# water_controller.net
KiCad netlist of a schematic drawn in EAGLE
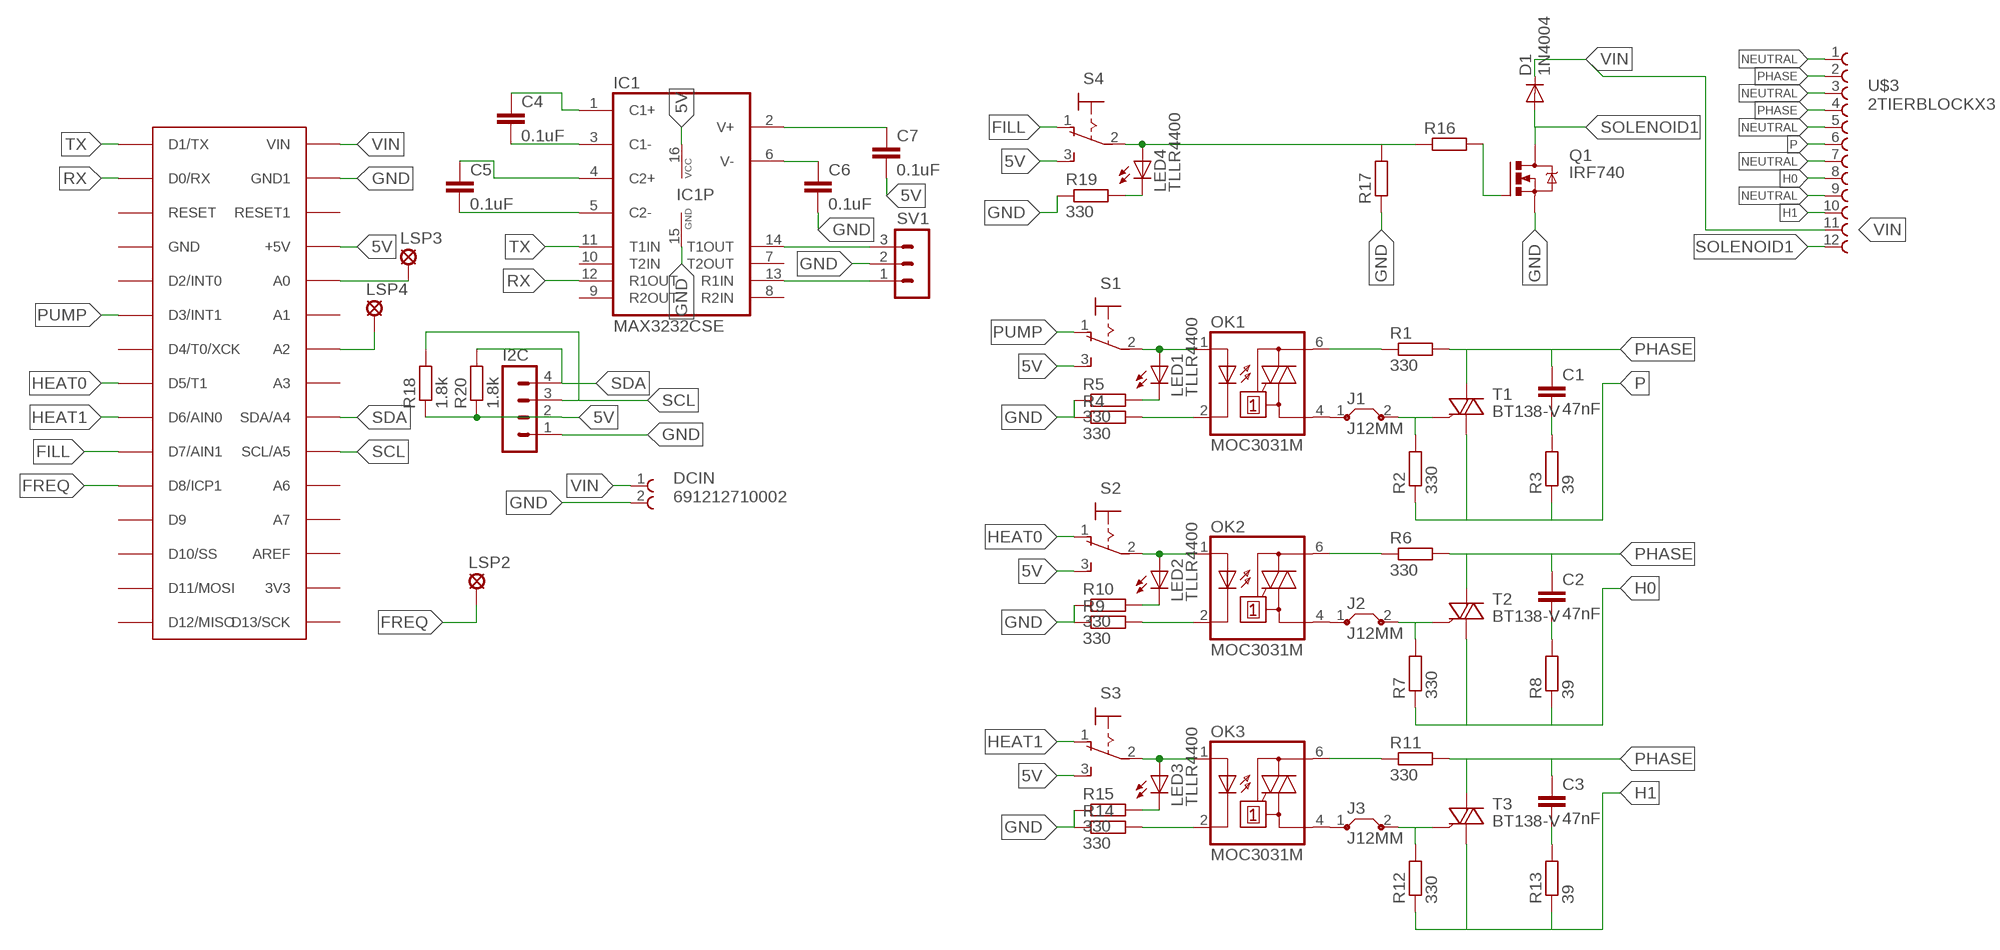
[diagram p0: schematic, sheet 1]

(export (version "E")
  (design (tool "Eeschema 10.0.6"))
  (components
    (comp (ref "C1")
      (value "47nF")
      (footprint "eagle-import:C150-064X183")
      (libsource (lib "eagle-import") (part "C-EU150-064X183"))
    )
    (comp (ref "C2")
      (value "47nF")
      (footprint "eagle-import:C150-064X183")
      (libsource (lib "eagle-import") (part "C-EU150-064X183"))
    )
    (comp (ref "C3")
      (value "47nF")
      (footprint "eagle-import:C150-064X183")
      (libsource (lib "eagle-import") (part "C-EU150-064X183"))
    )
    (comp (ref "C4")
      (value "0.1uF")
      (footprint "eagle-import:C0805")
      (libsource (lib "eagle-import") (part "C-EUC0805"))
    )
    (comp (ref "C5")
      (value "0.1uF")
      (footprint "eagle-import:C0805")
      (libsource (lib "eagle-import") (part "C-EUC0805"))
    )
    (comp (ref "C6")
      (value "0.1uF")
      (footprint "eagle-import:C0805")
      (libsource (lib "eagle-import") (part "C-EUC0805"))
    )
    (comp (ref "C7")
      (value "0.1uF")
      (footprint "eagle-import:C0805")
      (libsource (lib "eagle-import") (part "C-EUC0805"))
    )
    (comp (ref "D1")
      (value "1N4004")
      (footprint "eagle-import:DO41-10")
      (libsource (lib "eagle-import") (part "1N4004"))
    )
    (comp (ref "DCIN")
      (value "691212710002")
      (footprint "eagle-import:691212710002")
      (libsource (lib "eagle-import") (part "691212710002"))
    )
    (comp (ref "I2C")
      (value "MA04-1")
      (footprint "eagle-import:MA04-1")
      (libsource (lib "eagle-import") (part "MA04-1"))
    )
    (comp (ref "IC1")
      (value "MAX3232CSE")
      (footprint "eagle-import:SO16")
      (libsource (lib "eagle-import") (part "MAX3232SEC"))
    )
    (comp (ref "J1")
      (value "J12MM")
      (footprint "eagle-import:12")
      (libsource (lib "eagle-import") (part "J12MM"))
    )
    (comp (ref "J2")
      (value "J12MM")
      (footprint "eagle-import:12")
      (libsource (lib "eagle-import") (part "J12MM"))
    )
    (comp (ref "J3")
      (value "J12MM")
      (footprint "eagle-import:12")
      (libsource (lib "eagle-import") (part "J12MM"))
    )
    (comp (ref "LED1")
      (value "TLLR4400")
      (footprint "eagle-import:LED3MM")
      (fields (field (name "MF") "VISHAY SEMICONDUCTOR"))
      (libsource (lib "eagle-import") (part "TLLR4400"))
    )
    (comp (ref "LED2")
      (value "TLLR4400")
      (footprint "eagle-import:LED3MM")
      (fields (field (name "MF") "VISHAY SEMICONDUCTOR"))
      (libsource (lib "eagle-import") (part "TLLR4400"))
    )
    (comp (ref "LED3")
      (value "TLLR4400")
      (footprint "eagle-import:LED3MM")
      (fields (field (name "MF") "VISHAY SEMICONDUCTOR"))
      (libsource (lib "eagle-import") (part "TLLR4400"))
    )
    (comp (ref "LED4")
      (value "TLLR4400")
      (footprint "eagle-import:LED3MM")
      (fields (field (name "MF") "VISHAY SEMICONDUCTOR"))
      (libsource (lib "eagle-import") (part "TLLR4400"))
    )
    (comp (ref "LSP2")
      (value "LSP11")
      (footprint "eagle-import:LSP11")
      (libsource (lib "eagle-import") (part "LSP11"))
    )
    (comp (ref "LSP3")
      (value "LSP11")
      (footprint "eagle-import:LSP11")
      (libsource (lib "eagle-import") (part "LSP11"))
    )
    (comp (ref "LSP4")
      (value "LSP11")
      (footprint "eagle-import:LSP11")
      (libsource (lib "eagle-import") (part "LSP11"))
    )
    (comp (ref "OK1")
      (value "MOC3031M")
      (footprint "eagle-import:DIL06")
      (fields (field (name "MF") "FAIRCHILD SEMICONDUCTOR") (field (name "MPN") "MOC3063"))
      (libsource (lib "eagle-import") (part "MOC3031M"))
    )
    (comp (ref "OK2")
      (value "MOC3031M")
      (footprint "eagle-import:DIL06")
      (fields (field (name "MF") "FAIRCHILD SEMICONDUCTOR") (field (name "MPN") "MOC3063"))
      (libsource (lib "eagle-import") (part "MOC3031M"))
    )
    (comp (ref "OK3")
      (value "MOC3031M")
      (footprint "eagle-import:DIL06")
      (fields (field (name "MF") "FAIRCHILD SEMICONDUCTOR") (field (name "MPN") "MOC3063"))
      (libsource (lib "eagle-import") (part "MOC3031M"))
    )
    (comp (ref "Q1")
      (value "IRF740")
      (footprint "eagle-import:TO220BV")
      (libsource (lib "eagle-import") (part "IRF740"))
    )
    (comp (ref "R1")
      (value "330")
      (footprint "eagle-import:M1206")
      (libsource (lib "eagle-import") (part "R-EU_M1206"))
    )
    (comp (ref "R2")
      (value "330")
      (footprint "eagle-import:M1206")
      (libsource (lib "eagle-import") (part "R-EU_M1206"))
    )
    (comp (ref "R3")
      (value "39")
      (footprint "eagle-import:M1206")
      (libsource (lib "eagle-import") (part "R-EU_M1206"))
    )
    (comp (ref "R4")
      (value "330")
      (footprint "eagle-import:R1206")
      (libsource (lib "eagle-import") (part "R-EU_R1206"))
    )
    (comp (ref "R5")
      (value "330")
      (footprint "eagle-import:R1206")
      (libsource (lib "eagle-import") (part "R-EU_R1206"))
    )
    (comp (ref "R6")
      (value "330")
      (footprint "eagle-import:M1206")
      (libsource (lib "eagle-import") (part "R-EU_M1206"))
    )
    (comp (ref "R7")
      (value "330")
      (footprint "eagle-import:M1206")
      (libsource (lib "eagle-import") (part "R-EU_M1206"))
    )
    (comp (ref "R8")
      (value "39")
      (footprint "eagle-import:M1206")
      (libsource (lib "eagle-import") (part "R-EU_M1206"))
    )
    (comp (ref "R9")
      (value "330")
      (footprint "eagle-import:R1206")
      (libsource (lib "eagle-import") (part "R-EU_R1206"))
    )
    (comp (ref "R10")
      (value "330")
      (footprint "eagle-import:R1206")
      (libsource (lib "eagle-import") (part "R-EU_R1206"))
    )
    (comp (ref "R11")
      (value "330")
      (footprint "eagle-import:M1206")
      (libsource (lib "eagle-import") (part "R-EU_M1206"))
    )
    (comp (ref "R12")
      (value "330")
      (footprint "eagle-import:M1206")
      (libsource (lib "eagle-import") (part "R-EU_M1206"))
    )
    (comp (ref "R13")
      (value "39")
      (footprint "eagle-import:M1206")
      (libsource (lib "eagle-import") (part "R-EU_M1206"))
    )
    (comp (ref "R14")
      (value "330")
      (footprint "eagle-import:R1206")
      (libsource (lib "eagle-import") (part "R-EU_R1206"))
    )
    (comp (ref "R15")
      (value "330")
      (footprint "eagle-import:R1206")
      (libsource (lib "eagle-import") (part "R-EU_R1206"))
    )
    (comp (ref "R16")
      (value "R-EU_0204/7")
      (footprint "eagle-import:0204_7")
      (libsource (lib "eagle-import") (part "R-EU_0204/7"))
    )
    (comp (ref "R17")
      (value "R-EU_M1206")
      (footprint "eagle-import:M1206")
      (libsource (lib "eagle-import") (part "R-EU_M1206"))
    )
    (comp (ref "R18")
      (value "1.8k")
      (footprint "eagle-import:R1206")
      (libsource (lib "eagle-import") (part "resistor_R-EU_R1206"))
    )
    (comp (ref "R19")
      (value "330")
      (footprint "eagle-import:R1206")
      (libsource (lib "eagle-import") (part "R-EU_R1206"))
    )
    (comp (ref "R20")
      (value "1.8k")
      (footprint "eagle-import:R1206")
      (libsource (lib "eagle-import") (part "resistor_R-EU_R1206"))
    )
    (comp (ref "S1")
      (value "M9040P")
      (footprint "eagle-import:M9040P")
      (libsource (lib "eagle-import") (part "M9040P"))
    )
    (comp (ref "S2")
      (value "M9040P")
      (footprint "eagle-import:M9040P")
      (libsource (lib "eagle-import") (part "M9040P"))
    )
    (comp (ref "S3")
      (value "M9040P")
      (footprint "eagle-import:M9040P")
      (libsource (lib "eagle-import") (part "M9040P"))
    )
    (comp (ref "S4")
      (value "M9040P")
      (footprint "eagle-import:M9040P")
      (libsource (lib "eagle-import") (part "M9040P"))
    )
    (comp (ref "SV1")
      (value "MA03-1")
      (footprint "eagle-import:MA03-1")
      (libsource (lib "eagle-import") (part "MA03-1"))
    )
    (comp (ref "T1")
      (value "BT138-V")
      (footprint "eagle-import:TO220BV")
      (libsource (lib "eagle-import") (part "BT138-V"))
    )
    (comp (ref "T2")
      (value "BT138-V")
      (footprint "eagle-import:TO220BV")
      (libsource (lib "eagle-import") (part "BT138-V"))
    )
    (comp (ref "T3")
      (value "BT138-V")
      (footprint "eagle-import:TO220BV")
      (libsource (lib "eagle-import") (part "BT138-V"))
    )
    (comp (ref "U$1")
      (value "ARDUINONANO")
      (footprint "eagle-import:PDIP-32")
      (libsource (lib "eagle-import") (part "ARDUINONANO"))
    )
    (comp (ref "U$3")
      (value "2TIERBLOCKX3")
      (footprint "eagle-import:2TIERX3")
      (libsource (lib "eagle-import") (part "2TIERBLOCKX3"))
    )
  )
  (nets
    (net (code "1") (name "5V") (class "Default")
      (node (ref "C7") (pin "2") (pinfunction "2_2") (pintype "passive"))
      (node (ref "I2C") (pin "2") (pinfunction "2_2") (pintype "passive"))
      (node (ref "IC1") (pin "16") (pinfunction "VCC_16") (pintype "power_in"))
      (node (ref "R18") (pin "1") (pinfunction "1_1") (pintype "passive"))
      (node (ref "R20") (pin "1") (pinfunction "1_1") (pintype "passive"))
      (node (ref "S1") (pin "3") (pinfunction "S_3") (pintype "passive"))
      (node (ref "S2") (pin "3") (pinfunction "S_3") (pintype "passive"))
      (node (ref "S3") (pin "3") (pinfunction "S_3") (pintype "passive"))
      (node (ref "S4") (pin "3") (pinfunction "S_3") (pintype "passive"))
      (node (ref "U$1") (pin "+5V") (pinfunction "+5V_+5V") (pintype "bidirectional"))
    )
    (net (code "2") (name "FILL") (class "Default")
      (node (ref "S4") (pin "1") (pinfunction "O_1") (pintype "passive"))
      (node (ref "U$1") (pin "D7") (pinfunction "D7/AIN1_D7") (pintype "bidirectional"))
    )
    (net (code "3") (name "FREQ") (class "Default")
      (node (ref "LSP2") (pin "MP") (pinfunction "MP_MP") (pintype "passive"))
      (node (ref "U$1") (pin "D8") (pinfunction "D8/ICP1_D8") (pintype "bidirectional"))
    )
    (net (code "4") (name "GND") (class "Default")
      (node (ref "C6") (pin "2") (pinfunction "2_2") (pintype "passive"))
      (node (ref "DCIN") (pin "2") (pinfunction "2_2") (pintype "passive"))
      (node (ref "I2C") (pin "1") (pinfunction "1_1") (pintype "passive"))
      (node (ref "IC1") (pin "15") (pinfunction "GND_15") (pintype "power_in"))
      (node (ref "Q1") (pin "S") (pinfunction "S_S") (pintype "passive"))
      (node (ref "R10") (pin "1") (pinfunction "1_1") (pintype "passive"))
      (node (ref "R14") (pin "1") (pinfunction "1_1") (pintype "passive"))
      (node (ref "R15") (pin "1") (pinfunction "1_1") (pintype "passive"))
      (node (ref "R17") (pin "1") (pinfunction "1_1") (pintype "passive"))
      (node (ref "R19") (pin "1") (pinfunction "1_1") (pintype "passive"))
      (node (ref "R4") (pin "1") (pinfunction "1_1") (pintype "passive"))
      (node (ref "R5") (pin "1") (pinfunction "1_1") (pintype "passive"))
      (node (ref "R9") (pin "1") (pinfunction "1_1") (pintype "passive"))
      (node (ref "SV1") (pin "2") (pinfunction "2_2") (pintype "passive"))
      (node (ref "U$1") (pin "GND1") (pinfunction "GND1_GND1") (pintype "bidirectional"))
    )
    (net (code "5") (name "H0") (class "Default")
      (node (ref "R7") (pin "1") (pinfunction "1_1") (pintype "passive"))
      (node (ref "R8") (pin "1") (pinfunction "1_1") (pintype "passive"))
      (node (ref "T2") (pin "T1") (pinfunction "A1_T1") (pintype "passive"))
      (node (ref "U$3") (pin "8") (pinfunction "8_8") (pintype "passive"))
    )
    (net (code "6") (name "H1") (class "Default")
      (node (ref "R12") (pin "1") (pinfunction "1_1") (pintype "passive"))
      (node (ref "R13") (pin "1") (pinfunction "1_1") (pintype "passive"))
      (node (ref "T3") (pin "T1") (pinfunction "A1_T1") (pintype "passive"))
      (node (ref "U$3") (pin "10") (pinfunction "10_10") (pintype "passive"))
    )
    (net (code "7") (name "HEAT0") (class "Default")
      (node (ref "S2") (pin "1") (pinfunction "O_1") (pintype "passive"))
      (node (ref "U$1") (pin "D5") (pinfunction "D5/T1_D5") (pintype "bidirectional"))
    )
    (net (code "8") (name "HEAT1") (class "Default")
      (node (ref "S3") (pin "1") (pinfunction "O_1") (pintype "passive"))
      (node (ref "U$1") (pin "D6") (pinfunction "D6/AIN0_D6") (pintype "bidirectional"))
    )
    (net (code "9") (name "NEUTRAL") (class "Default")
      (node (ref "U$3") (pin "1") (pinfunction "1_1") (pintype "passive"))
      (node (ref "U$3") (pin "3") (pinfunction "3_3") (pintype "passive"))
      (node (ref "U$3") (pin "5") (pinfunction "5_5") (pintype "passive"))
      (node (ref "U$3") (pin "7") (pinfunction "7_7") (pintype "passive"))
      (node (ref "U$3") (pin "9") (pinfunction "9_9") (pintype "passive"))
    )
    (net (code "10") (name "Net-(C1-Pad2)") (class "Default")
      (node (ref "C1") (pin "2") (pinfunction "2_2") (pintype "passive"))
      (node (ref "R3") (pin "2") (pinfunction "2_2") (pintype "passive"))
    )
    (net (code "11") (name "Net-(C2-Pad2)") (class "Default")
      (node (ref "C2") (pin "2") (pinfunction "2_2") (pintype "passive"))
      (node (ref "R8") (pin "2") (pinfunction "2_2") (pintype "passive"))
    )
    (net (code "12") (name "Net-(C3-Pad2)") (class "Default")
      (node (ref "C3") (pin "2") (pinfunction "2_2") (pintype "passive"))
      (node (ref "R13") (pin "2") (pinfunction "2_2") (pintype "passive"))
    )
    (net (code "13") (name "Net-(IC1A-C1+)") (class "Default")
      (node (ref "C4") (pin "1") (pinfunction "1_1") (pintype "passive"))
      (node (ref "IC1") (pin "1") (pinfunction "C1+_1") (pintype "bidirectional"))
    )
    (net (code "14") (name "Net-(IC1A-C1-)") (class "Default")
      (node (ref "C4") (pin "2") (pinfunction "2_2") (pintype "passive"))
      (node (ref "IC1") (pin "3") (pinfunction "C1-_3") (pintype "bidirectional"))
    )
    (net (code "15") (name "Net-(IC1A-C2+)") (class "Default")
      (node (ref "C5") (pin "1") (pinfunction "1_1") (pintype "passive"))
      (node (ref "IC1") (pin "4") (pinfunction "C2+_4") (pintype "bidirectional"))
    )
    (net (code "16") (name "Net-(IC1A-C2-)") (class "Default")
      (node (ref "C5") (pin "2") (pinfunction "2_2") (pintype "passive"))
      (node (ref "IC1") (pin "5") (pinfunction "C2-_5") (pintype "bidirectional"))
    )
    (net (code "17") (name "Net-(IC1A-R1IN)") (class "Default")
      (node (ref "IC1") (pin "13") (pinfunction "R1IN_13") (pintype "input"))
      (node (ref "SV1") (pin "1") (pinfunction "1_1") (pintype "passive"))
    )
    (net (code "18") (name "Net-(IC1A-T1OUT)") (class "Default")
      (node (ref "IC1") (pin "14") (pinfunction "T1OUT_14") (pintype "output"))
      (node (ref "SV1") (pin "3") (pinfunction "3_3") (pintype "passive"))
    )
    (net (code "19") (name "Net-(IC1A-V+)") (class "Default")
      (node (ref "C7") (pin "1") (pinfunction "1_1") (pintype "passive"))
      (node (ref "IC1") (pin "2") (pinfunction "V+_2") (pintype "bidirectional"))
    )
    (net (code "20") (name "Net-(IC1A-V-)") (class "Default")
      (node (ref "C6") (pin "1") (pinfunction "1_1") (pintype "passive"))
      (node (ref "IC1") (pin "6") (pinfunction "V-_6") (pintype "bidirectional"))
    )
    (net (code "21") (name "Net-(J1-Pad2)") (class "Default")
      (node (ref "J1") (pin "2") (pinfunction "2_2") (pintype "passive"))
      (node (ref "R2") (pin "2") (pinfunction "2_2") (pintype "passive"))
      (node (ref "T1") (pin "G") (pinfunction "G_G") (pintype "passive"))
    )
    (net (code "22") (name "Net-(J2-Pad2)") (class "Default")
      (node (ref "J2") (pin "2") (pinfunction "2_2") (pintype "passive"))
      (node (ref "R7") (pin "2") (pinfunction "2_2") (pintype "passive"))
      (node (ref "T2") (pin "G") (pinfunction "G_G") (pintype "passive"))
    )
    (net (code "23") (name "Net-(J3-Pad2)") (class "Default")
      (node (ref "J3") (pin "2") (pinfunction "2_2") (pintype "passive"))
      (node (ref "R12") (pin "2") (pinfunction "2_2") (pintype "passive"))
      (node (ref "T3") (pin "G") (pinfunction "G_G") (pintype "passive"))
    )
    (net (code "24") (name "Net-(LED1-C)") (class "Default")
      (node (ref "LED1") (pin "K") (pinfunction "C_K") (pintype "passive"))
      (node (ref "R5") (pin "2") (pinfunction "2_2") (pintype "passive"))
    )
    (net (code "25") (name "Net-(LED2-C)") (class "Default")
      (node (ref "LED2") (pin "K") (pinfunction "C_K") (pintype "passive"))
      (node (ref "R10") (pin "2") (pinfunction "2_2") (pintype "passive"))
    )
    (net (code "26") (name "Net-(LED3-C)") (class "Default")
      (node (ref "LED3") (pin "K") (pinfunction "C_K") (pintype "passive"))
      (node (ref "R15") (pin "2") (pinfunction "2_2") (pintype "passive"))
    )
    (net (code "27") (name "Net-(LED4-C)") (class "Default")
      (node (ref "LED4") (pin "K") (pinfunction "C_K") (pintype "passive"))
      (node (ref "R19") (pin "2") (pinfunction "2_2") (pintype "passive"))
    )
    (net (code "28") (name "Net-(LSP3-PadMP)") (class "Default")
      (node (ref "LSP3") (pin "MP") (pinfunction "MP_MP") (pintype "passive"))
      (node (ref "U$1") (pin "A0") (pinfunction "A0_A0") (pintype "bidirectional"))
    )
    (net (code "29") (name "Net-(LSP4-PadMP)") (class "Default")
      (node (ref "LSP4") (pin "MP") (pinfunction "MP_MP") (pintype "passive"))
      (node (ref "U$1") (pin "A2") (pinfunction "A2_A2") (pintype "bidirectional"))
    )
    (net (code "30") (name "Net-(OK1-A)") (class "Default")
      (node (ref "LED1") (pin "A") (pinfunction "A_A") (pintype "passive"))
      (node (ref "OK1") (pin "1") (pinfunction "A_1") (pintype "passive"))
      (node (ref "S1") (pin "2") (pinfunction "P_2") (pintype "passive"))
    )
    (net (code "31") (name "Net-(OK1-A1)") (class "Default")
      (node (ref "J1") (pin "1") (pinfunction "1_1") (pintype "passive"))
      (node (ref "OK1") (pin "4") (pinfunction "A1_4") (pintype "passive"))
    )
    (net (code "32") (name "Net-(OK1-A2)") (class "Default")
      (node (ref "OK1") (pin "6") (pinfunction "A2_6") (pintype "passive"))
      (node (ref "R1") (pin "1") (pinfunction "1_1") (pintype "passive"))
    )
    (net (code "33") (name "Net-(OK1-C)") (class "Default")
      (node (ref "OK1") (pin "2") (pinfunction "C_2") (pintype "passive"))
      (node (ref "R4") (pin "2") (pinfunction "2_2") (pintype "passive"))
    )
    (net (code "34") (name "Net-(OK2-A)") (class "Default")
      (node (ref "LED2") (pin "A") (pinfunction "A_A") (pintype "passive"))
      (node (ref "OK2") (pin "1") (pinfunction "A_1") (pintype "passive"))
      (node (ref "S2") (pin "2") (pinfunction "P_2") (pintype "passive"))
    )
    (net (code "35") (name "Net-(OK2-A1)") (class "Default")
      (node (ref "J2") (pin "1") (pinfunction "1_1") (pintype "passive"))
      (node (ref "OK2") (pin "4") (pinfunction "A1_4") (pintype "passive"))
    )
    (net (code "36") (name "Net-(OK2-A2)") (class "Default")
      (node (ref "OK2") (pin "6") (pinfunction "A2_6") (pintype "passive"))
      (node (ref "R6") (pin "1") (pinfunction "1_1") (pintype "passive"))
    )
    (net (code "37") (name "Net-(OK2-C)") (class "Default")
      (node (ref "OK2") (pin "2") (pinfunction "C_2") (pintype "passive"))
      (node (ref "R9") (pin "2") (pinfunction "2_2") (pintype "passive"))
    )
    (net (code "38") (name "Net-(OK3-A)") (class "Default")
      (node (ref "LED3") (pin "A") (pinfunction "A_A") (pintype "passive"))
      (node (ref "OK3") (pin "1") (pinfunction "A_1") (pintype "passive"))
      (node (ref "S3") (pin "2") (pinfunction "P_2") (pintype "passive"))
    )
    (net (code "39") (name "Net-(OK3-A1)") (class "Default")
      (node (ref "J3") (pin "1") (pinfunction "1_1") (pintype "passive"))
      (node (ref "OK3") (pin "4") (pinfunction "A1_4") (pintype "passive"))
    )
    (net (code "40") (name "Net-(OK3-A2)") (class "Default")
      (node (ref "OK3") (pin "6") (pinfunction "A2_6") (pintype "passive"))
      (node (ref "R11") (pin "1") (pinfunction "1_1") (pintype "passive"))
    )
    (net (code "41") (name "Net-(OK3-C)") (class "Default")
      (node (ref "OK3") (pin "2") (pinfunction "C_2") (pintype "passive"))
      (node (ref "R14") (pin "2") (pinfunction "2_2") (pintype "passive"))
    )
    (net (code "42") (name "Net-(Q1-PadG)") (class "Default")
      (node (ref "Q1") (pin "G") (pinfunction "G_G") (pintype "passive"))
      (node (ref "R16") (pin "2") (pinfunction "2_2") (pintype "passive"))
    )
    (net (code "43") (name "Net-(S4-P)") (class "Default")
      (node (ref "LED4") (pin "A") (pinfunction "A_A") (pintype "passive"))
      (node (ref "R16") (pin "1") (pinfunction "1_1") (pintype "passive"))
      (node (ref "R17") (pin "2") (pinfunction "2_2") (pintype "passive"))
      (node (ref "S4") (pin "2") (pinfunction "P_2") (pintype "passive"))
    )
    (net (code "44") (name "P") (class "Default")
      (node (ref "R2") (pin "1") (pinfunction "1_1") (pintype "passive"))
      (node (ref "R3") (pin "1") (pinfunction "1_1") (pintype "passive"))
      (node (ref "T1") (pin "T1") (pinfunction "A1_T1") (pintype "passive"))
      (node (ref "U$3") (pin "6") (pinfunction "6_6") (pintype "passive"))
    )
    (net (code "45") (name "PHASE") (class "Default")
      (node (ref "C1") (pin "1") (pinfunction "1_1") (pintype "passive"))
      (node (ref "C2") (pin "1") (pinfunction "1_1") (pintype "passive"))
      (node (ref "C3") (pin "1") (pinfunction "1_1") (pintype "passive"))
      (node (ref "R1") (pin "2") (pinfunction "2_2") (pintype "passive"))
      (node (ref "R11") (pin "2") (pinfunction "2_2") (pintype "passive"))
      (node (ref "R6") (pin "2") (pinfunction "2_2") (pintype "passive"))
      (node (ref "T1") (pin "T2") (pinfunction "A2_T2") (pintype "passive"))
      (node (ref "T2") (pin "T2") (pinfunction "A2_T2") (pintype "passive"))
      (node (ref "T3") (pin "T2") (pinfunction "A2_T2") (pintype "passive"))
      (node (ref "U$3") (pin "2") (pinfunction "2_2") (pintype "passive"))
      (node (ref "U$3") (pin "4") (pinfunction "4_4") (pintype "passive"))
    )
    (net (code "46") (name "PUMP") (class "Default")
      (node (ref "S1") (pin "1") (pinfunction "O_1") (pintype "passive"))
      (node (ref "U$1") (pin "D3") (pinfunction "D3/INT1_D3") (pintype "bidirectional"))
    )
    (net (code "47") (name "RX") (class "Default")
      (node (ref "IC1") (pin "12") (pinfunction "R1OUT_12") (pintype "output"))
      (node (ref "U$1") (pin "D0/RX") (pinfunction "D0/RX_D0/RX") (pintype "bidirectional"))
    )
    (net (code "48") (name "SCL") (class "Default")
      (node (ref "I2C") (pin "3") (pinfunction "3_3") (pintype "passive"))
      (node (ref "R18") (pin "2") (pinfunction "2_2") (pintype "passive"))
      (node (ref "U$1") (pin "A5") (pinfunction "SCL/A5_A5") (pintype "bidirectional"))
    )
    (net (code "49") (name "SDA") (class "Default")
      (node (ref "I2C") (pin "4") (pinfunction "4_4") (pintype "passive"))
      (node (ref "R20") (pin "2") (pinfunction "2_2") (pintype "passive"))
      (node (ref "U$1") (pin "A4") (pinfunction "SDA/A4_A4") (pintype "bidirectional"))
    )
    (net (code "50") (name "SOLENOID1") (class "Default")
      (node (ref "D1") (pin "A") (pinfunction "A_A") (pintype "passive"))
      (node (ref "Q1") (pin "D") (pinfunction "D_D") (pintype "passive"))
      (node (ref "U$3") (pin "12") (pinfunction "12_12") (pintype "passive"))
    )
    (net (code "51") (name "TX") (class "Default")
      (node (ref "IC1") (pin "11") (pinfunction "T1IN_11") (pintype "input"))
      (node (ref "U$1") (pin "D1/TX") (pinfunction "D1/TX_D1/TX") (pintype "bidirectional"))
    )
    (net (code "52") (name "VIN") (class "Default")
      (node (ref "D1") (pin "C") (pinfunction "C_C") (pintype "passive"))
      (node (ref "DCIN") (pin "1") (pinfunction "1_1") (pintype "passive"))
      (node (ref "U$1") (pin "VIN") (pinfunction "VIN_VIN") (pintype "bidirectional"))
      (node (ref "U$3") (pin "11") (pinfunction "11_11") (pintype "passive"))
    )
    (net (code "53") (name "unconnected-(IC1A-R2IN-Pad8)") (class "Default")
      (node (ref "IC1") (pin "8") (pinfunction "R2IN_8") (pintype "input"))
    )
    (net (code "54") (name "unconnected-(IC1A-R2OUT-Pad9)") (class "Default")
      (node (ref "IC1") (pin "9") (pinfunction "R2OUT_9") (pintype "output"))
    )
    (net (code "55") (name "unconnected-(IC1A-T2IN-Pad10)") (class "Default")
      (node (ref "IC1") (pin "10") (pinfunction "T2IN_10") (pintype "input"))
    )
    (net (code "56") (name "unconnected-(IC1A-T2OUT-Pad7)") (class "Default")
      (node (ref "IC1") (pin "7") (pinfunction "T2OUT_7") (pintype "output"))
    )
    (net (code "57") (name "unconnected-(U$1-D2{slash}INT0-PadD2)") (class "Default")
      (node (ref "U$1") (pin "D2") (pinfunction "D2/INT0_D2") (pintype "bidirectional"))
    )
    (net (code "58") (name "unconnected-(U$1-D4{slash}T0{slash}XCK-PadD4)") (class "Default")
      (node (ref "U$1") (pin "D4") (pinfunction "D4/T0/XCK_D4") (pintype "bidirectional"))
    )
    (net (code "59") (name "unconnected-(U$1-D10{slash}SS-PadD10)") (class "Default")
      (node (ref "U$1") (pin "D10") (pinfunction "D10/SS_D10") (pintype "bidirectional"))
    )
    (net (code "60") (name "unconnected-(U$1-D11{slash}MOSI-PadD11)") (class "Default")
      (node (ref "U$1") (pin "D11") (pinfunction "D11/MOSI_D11") (pintype "bidirectional"))
    )
    (net (code "61") (name "unconnected-(U$1-D12{slash}MISO-PadD12)") (class "Default")
      (node (ref "U$1") (pin "D12") (pinfunction "D12/MISO_D12") (pintype "bidirectional"))
    )
    (net (code "62") (name "unconnected-(U$1-D13{slash}SCK-PadD13)") (class "Default")
      (node (ref "U$1") (pin "D13") (pinfunction "D13/SCK_D13") (pintype "bidirectional"))
    )
    (net (code "63") (name "unconnected-(U$1-Pad3V3)") (class "Default")
      (node (ref "U$1") (pin "3V3") (pinfunction "3V3_3V3") (pintype "bidirectional"))
    )
    (net (code "64") (name "unconnected-(U$1-PadA1)") (class "Default")
      (node (ref "U$1") (pin "A1") (pinfunction "A1_A1") (pintype "bidirectional"))
    )
    (net (code "65") (name "unconnected-(U$1-PadA3)") (class "Default")
      (node (ref "U$1") (pin "A3") (pinfunction "A3_A3") (pintype "bidirectional"))
    )
    (net (code "66") (name "unconnected-(U$1-PadA6)") (class "Default")
      (node (ref "U$1") (pin "A6") (pinfunction "A6_A6") (pintype "bidirectional"))
    )
    (net (code "67") (name "unconnected-(U$1-PadA7)") (class "Default")
      (node (ref "U$1") (pin "A7") (pinfunction "A7_A7") (pintype "bidirectional"))
    )
    (net (code "68") (name "unconnected-(U$1-PadAREF)") (class "Default")
      (node (ref "U$1") (pin "AREF") (pinfunction "AREF_AREF") (pintype "bidirectional"))
    )
    (net (code "69") (name "unconnected-(U$1-PadD9)") (class "Default")
      (node (ref "U$1") (pin "D9") (pinfunction "D9_D9") (pintype "bidirectional"))
    )
    (net (code "70") (name "unconnected-(U$1-PadGND)") (class "Default")
      (node (ref "U$1") (pin "GND") (pinfunction "GND_GND") (pintype "bidirectional"))
    )
    (net (code "71") (name "unconnected-(U$1-PadRESET)") (class "Default")
      (node (ref "U$1") (pin "RESET") (pinfunction "RESET_RESET") (pintype "bidirectional"))
    )
    (net (code "72") (name "unconnected-(U$1-PadRESET1)") (class "Default")
      (node (ref "U$1") (pin "RESET1") (pinfunction "RESET1_RESET1") (pintype "bidirectional"))
    )
  )
)
